# HOLDUP.net
KiCad netlist of a schematic drawn in EAGLE
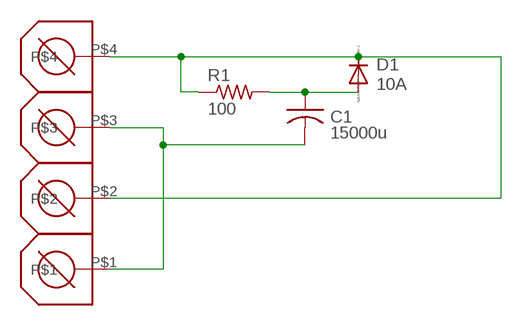
[diagram p0: schematic, sheet 1]

(export (version "E")
  (design (tool "Eeschema 10.0.6"))
  (components
    (comp (ref "C1")
      (value "15000u")
      (footprint "eagle-import:CAPPRD750W65D1800H3700B")
      (libsource (lib "eagle-import") (part "AIR_HOLDUP_CAP"))
    )
    (comp (ref "D1")
      (value "10A")
      (footprint "eagle-import:DIOAD1570W120L850D500B")
      (libsource (lib "eagle-import") (part "AIR_HOLDUP_DIODE"))
    )
    (comp (ref "J1")
      (value "TE_282834-4")
      (footprint "eagle-import:282834-4_FOOT")
      (libsource (lib "eagle-import") (part "TE_282834-4"))
    )
    (comp (ref "R1")
      (value "100")
      (footprint "eagle-import:RESAD976W63L650D250B")
      (libsource (lib "eagle-import") (part "AIR_HOLDUP_RESISTOR"))
    )
  )
  (nets
    (net (code "1") (name "Net-(C1-Pad2)") (class "Default")
      (node (ref "C1") (pin "2") (pinfunction "2_2") (pintype "passive"))
      (node (ref "J1") (pin "P$1") (pinfunction "P$1_P$1") (pintype "bidirectional"))
      (node (ref "J1") (pin "P$3") (pinfunction "P$3_P$3") (pintype "bidirectional"))
    )
    (net (code "2") (name "Net-(D1-A)") (class "Default")
      (node (ref "C1") (pin "1") (pinfunction "1_1") (pintype "passive"))
      (node (ref "D1") (pin "2") (pinfunction "A_2") (pintype "passive"))
      (node (ref "R1") (pin "2") (pinfunction "2_2") (pintype "passive"))
    )
    (net (code "3") (name "Net-(D1-C)") (class "Default")
      (node (ref "D1") (pin "1") (pinfunction "C_1") (pintype "passive"))
      (node (ref "J1") (pin "P$2") (pinfunction "P$2_P$2") (pintype "bidirectional"))
      (node (ref "J1") (pin "P$4") (pinfunction "P$4_P$4") (pintype "bidirectional"))
      (node (ref "R1") (pin "1") (pinfunction "1_1") (pintype "passive"))
    )
  )
)
